# NguyenLi.net
KiCad netlist of a schematic drawn in Altium Designer
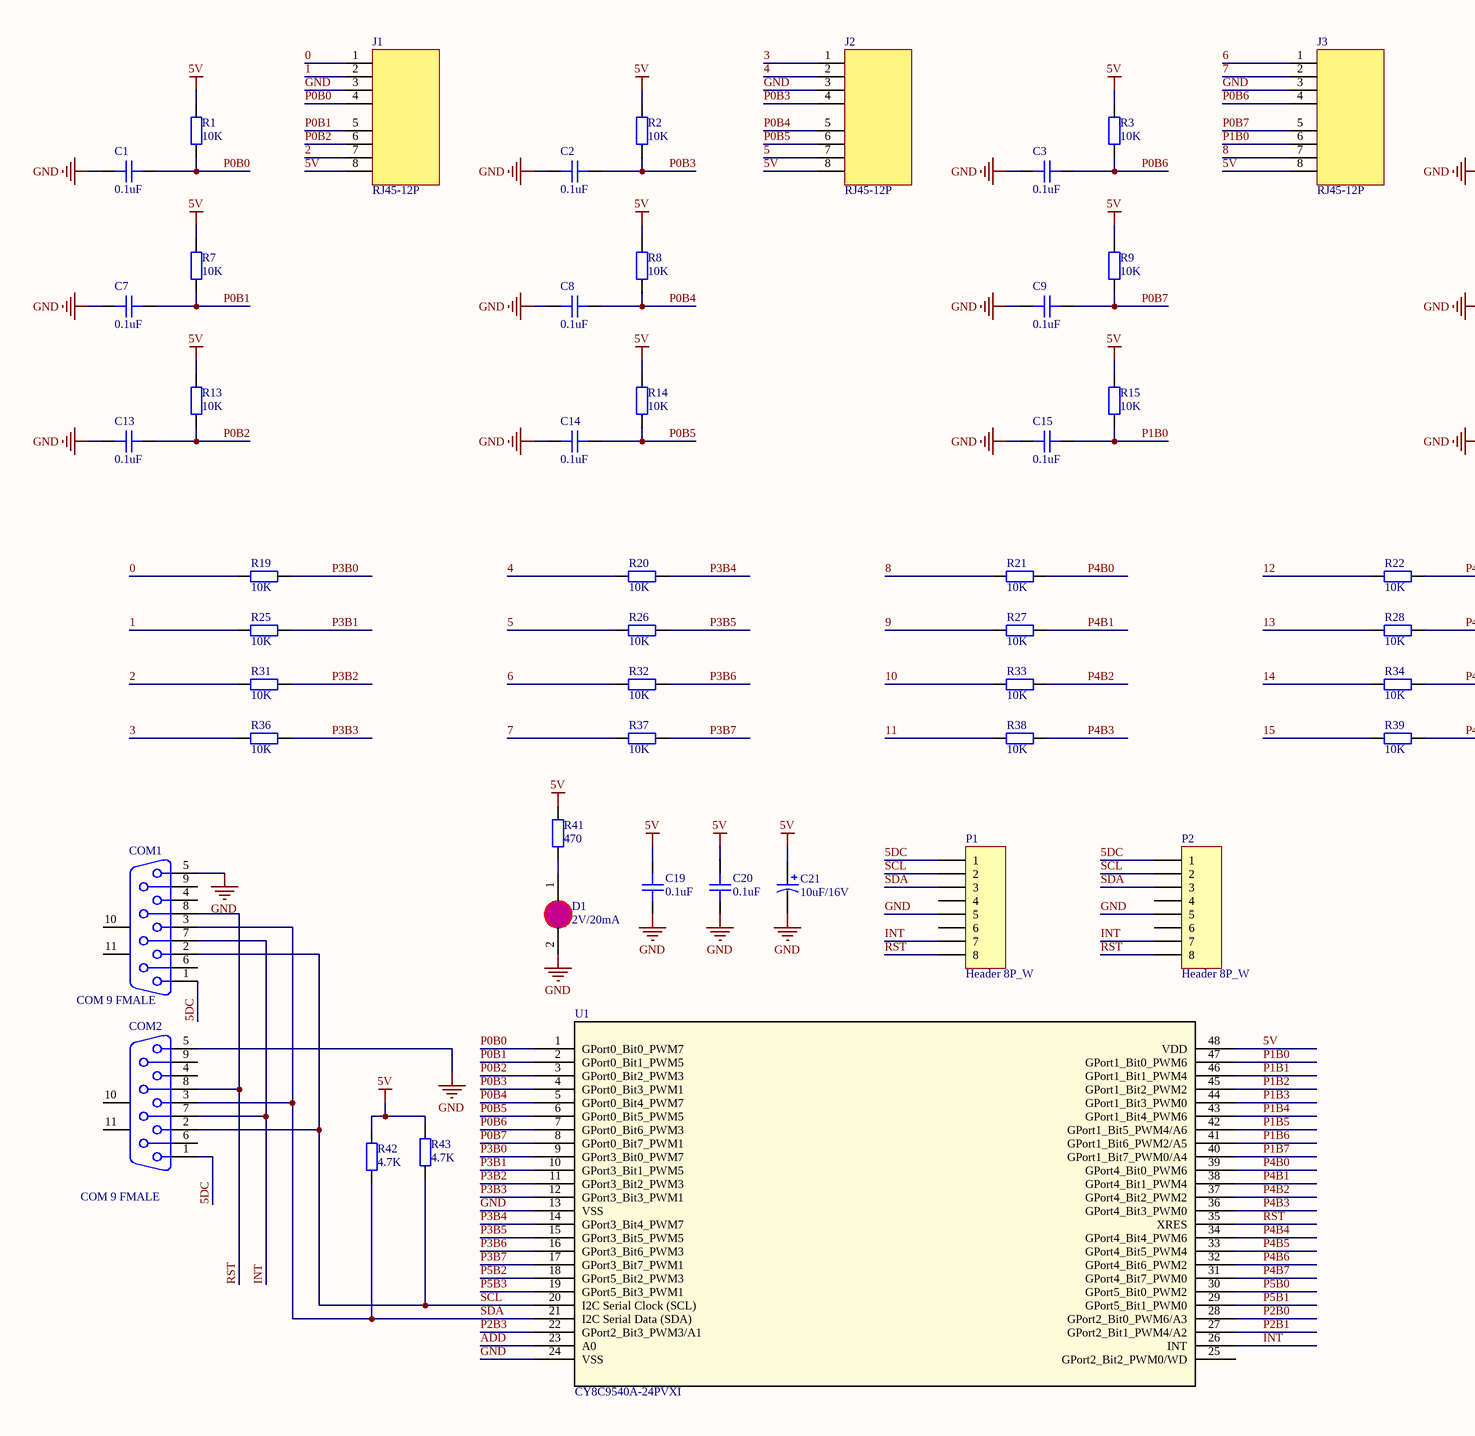
[diagram p0: NguyenLi.SchDoc, left]
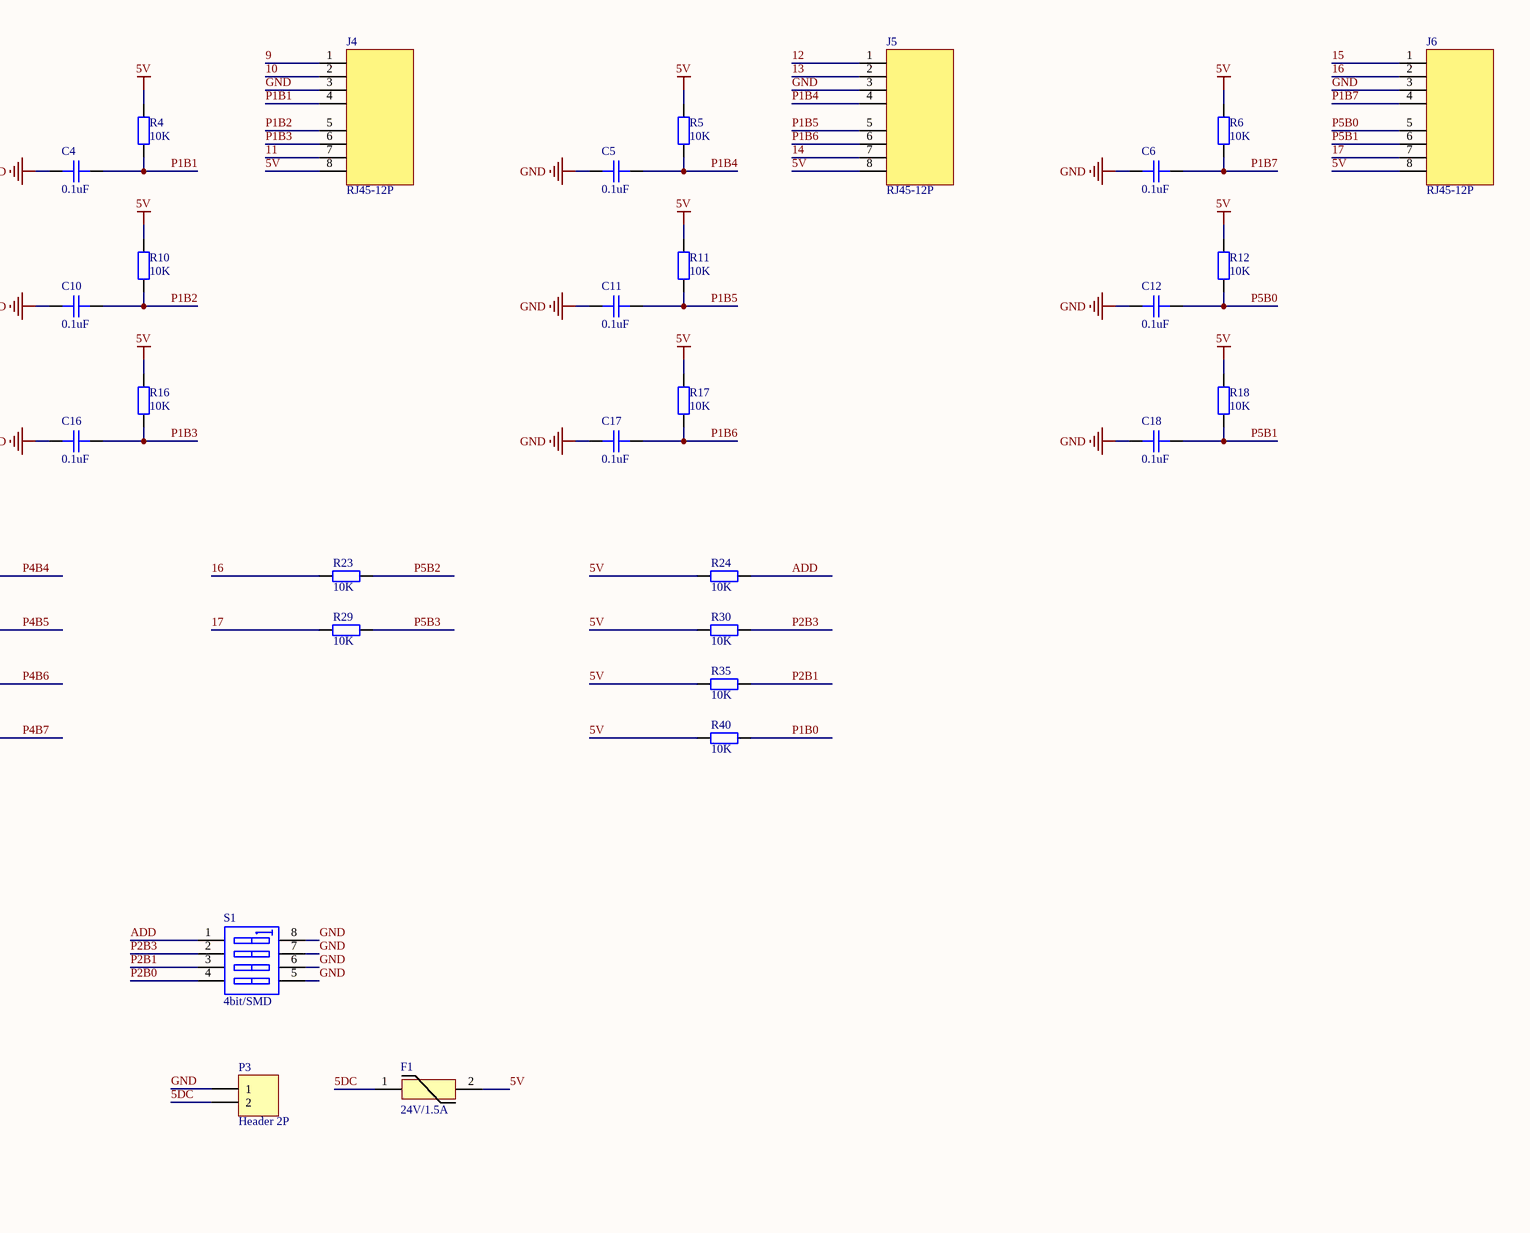
[diagram p1: NguyenLi.SchDoc, right]

(export (version "E")
  (design (tool "Eeschema 10.0.6"))
  (components
    (comp (ref "C1")
      (value "0.1uF")
      (footprint "CAPC-0603 (1608)")
      (description "CAP CER 0.1uF 50V 10% X7R 0603")
      (fields (field (name "MPN") "C0603C104K5RACTU"))
      (libsource (lib "BYTECH_HW_LIB_2019 (1) (1)") (part "C0603C104K5RACTU"))
    )
    (comp (ref "C2")
      (value "0.1uF")
      (footprint "CAPC-0603 (1608)")
      (description "CAP CER 0.1uF 50V 10% X7R 0603")
      (fields (field (name "MPN") "C0603C104K5RACTU"))
      (libsource (lib "BYTECH_HW_LIB_2019 (1) (1)") (part "C0603C104K5RACTU"))
    )
    (comp (ref "C3")
      (value "0.1uF")
      (footprint "CAPC-0603 (1608)")
      (description "CAP CER 0.1uF 50V 10% X7R 0603")
      (fields (field (name "MPN") "C0603C104K5RACTU"))
      (libsource (lib "BYTECH_HW_LIB_2019 (1) (1)") (part "C0603C104K5RACTU"))
    )
    (comp (ref "C4")
      (value "0.1uF")
      (footprint "CAPC-0603 (1608)")
      (description "CAP CER 0.1uF 50V 10% X7R 0603")
      (fields (field (name "MPN") "C0603C104K5RACTU"))
      (libsource (lib "BYTECH_HW_LIB_2019 (1) (1)") (part "C0603C104K5RACTU"))
    )
    (comp (ref "C5")
      (value "0.1uF")
      (footprint "CAPC-0603 (1608)")
      (description "CAP CER 0.1uF 50V 10% X7R 0603")
      (fields (field (name "MPN") "C0603C104K5RACTU"))
      (libsource (lib "BYTECH_HW_LIB_2019 (1) (1)") (part "C0603C104K5RACTU"))
    )
    (comp (ref "C6")
      (value "0.1uF")
      (footprint "CAPC-0603 (1608)")
      (description "CAP CER 0.1uF 50V 10% X7R 0603")
      (fields (field (name "MPN") "C0603C104K5RACTU"))
      (libsource (lib "BYTECH_HW_LIB_2019 (1) (1)") (part "C0603C104K5RACTU"))
    )
    (comp (ref "C7")
      (value "0.1uF")
      (footprint "CAPC-0603 (1608)")
      (description "CAP CER 0.1uF 50V 10% X7R 0603")
      (fields (field (name "MPN") "C0603C104K5RACTU"))
      (libsource (lib "BYTECH_HW_LIB_2019 (1) (1)") (part "C0603C104K5RACTU"))
    )
    (comp (ref "C8")
      (value "0.1uF")
      (footprint "CAPC-0603 (1608)")
      (description "CAP CER 0.1uF 50V 10% X7R 0603")
      (fields (field (name "MPN") "C0603C104K5RACTU"))
      (libsource (lib "BYTECH_HW_LIB_2019 (1) (1)") (part "C0603C104K5RACTU"))
    )
    (comp (ref "C9")
      (value "0.1uF")
      (footprint "CAPC-0603 (1608)")
      (description "CAP CER 0.1uF 50V 10% X7R 0603")
      (fields (field (name "MPN") "C0603C104K5RACTU"))
      (libsource (lib "BYTECH_HW_LIB_2019 (1) (1)") (part "C0603C104K5RACTU"))
    )
    (comp (ref "C10")
      (value "0.1uF")
      (footprint "CAPC-0603 (1608)")
      (description "CAP CER 0.1uF 50V 10% X7R 0603")
      (fields (field (name "MPN") "C0603C104K5RACTU"))
      (libsource (lib "BYTECH_HW_LIB_2019 (1) (1)") (part "C0603C104K5RACTU"))
    )
    (comp (ref "C11")
      (value "0.1uF")
      (footprint "CAPC-0603 (1608)")
      (description "CAP CER 0.1uF 50V 10% X7R 0603")
      (fields (field (name "MPN") "C0603C104K5RACTU"))
      (libsource (lib "BYTECH_HW_LIB_2019 (1) (1)") (part "C0603C104K5RACTU"))
    )
    (comp (ref "C12")
      (value "0.1uF")
      (footprint "CAPC-0603 (1608)")
      (description "CAP CER 0.1uF 50V 10% X7R 0603")
      (fields (field (name "MPN") "C0603C104K5RACTU"))
      (libsource (lib "BYTECH_HW_LIB_2019 (1) (1)") (part "C0603C104K5RACTU"))
    )
    (comp (ref "C13")
      (value "0.1uF")
      (footprint "CAPC-0603 (1608)")
      (description "CAP CER 0.1uF 50V 10% X7R 0603")
      (fields (field (name "MPN") "C0603C104K5RACTU"))
      (libsource (lib "BYTECH_HW_LIB_2019 (1) (1)") (part "C0603C104K5RACTU"))
    )
    (comp (ref "C14")
      (value "0.1uF")
      (footprint "CAPC-0603 (1608)")
      (description "CAP CER 0.1uF 50V 10% X7R 0603")
      (fields (field (name "MPN") "C0603C104K5RACTU"))
      (libsource (lib "BYTECH_HW_LIB_2019 (1) (1)") (part "C0603C104K5RACTU"))
    )
    (comp (ref "C15")
      (value "0.1uF")
      (footprint "CAPC-0603 (1608)")
      (description "CAP CER 0.1uF 50V 10% X7R 0603")
      (fields (field (name "MPN") "C0603C104K5RACTU"))
      (libsource (lib "BYTECH_HW_LIB_2019 (1) (1)") (part "C0603C104K5RACTU"))
    )
    (comp (ref "C16")
      (value "0.1uF")
      (footprint "CAPC-0603 (1608)")
      (description "CAP CER 0.1uF 50V 10% X7R 0603")
      (fields (field (name "MPN") "C0603C104K5RACTU"))
      (libsource (lib "BYTECH_HW_LIB_2019 (1) (1)") (part "C0603C104K5RACTU"))
    )
    (comp (ref "C17")
      (value "0.1uF")
      (footprint "CAPC-0603 (1608)")
      (description "CAP CER 0.1uF 50V 10% X7R 0603")
      (fields (field (name "MPN") "C0603C104K5RACTU"))
      (libsource (lib "BYTECH_HW_LIB_2019 (1) (1)") (part "C0603C104K5RACTU"))
    )
    (comp (ref "C18")
      (value "0.1uF")
      (footprint "CAPC-0603 (1608)")
      (description "CAP CER 0.1uF 50V 10% X7R 0603")
      (fields (field (name "MPN") "C0603C104K5RACTU"))
      (libsource (lib "BYTECH_HW_LIB_2019 (1) (1)") (part "C0603C104K5RACTU"))
    )
    (comp (ref "C19")
      (value "0.1uF")
      (footprint "CAPC-0603 (1608)")
      (description "CAP CER 0.1uF 50V 10% X7R 0603")
      (fields (field (name "MPN") "C0603C104K5RACTU"))
      (libsource (lib "BYTECH_HW_LIB_2019 (1) (1)") (part "C0603C104K5RACTU"))
    )
    (comp (ref "C20")
      (value "0.1uF")
      (footprint "CAPC-0603 (1608)")
      (description "CAP CER 0.1uF 50V 10% X7R 0603")
      (fields (field (name "MPN") "C0603C104K5RACTU"))
      (libsource (lib "BYTECH_HW_LIB_2019 (1) (1)") (part "C0603C104K5RACTU"))
    )
    (comp (ref "C21")
      (value "10uF/16V")
      (footprint "CAP_ALUM_D050_S20_H110")
      (description "CAP ALUM 10uF 50V 20% RADIAL")
      (fields (field (name "MPN") "106CKR050M"))
      (libsource (lib "BYTECH_HW_LIB_2019 (1) (1)") (part "106CKR050M"))
    )
    (comp (ref "COM1")
      (value "COM 9 FMALE")
      (footprint "DSB 9-F")
      (description "COM 9")
      (fields (field (name "PUBLISHER") "Altium Limited"))
      (libsource (lib "My Library") (part "DSB9F"))
    )
    (comp (ref "COM2")
      (value "COM 9 FMALE")
      (footprint "DSB 9-F")
      (description "COM 9")
      (fields (field (name "PUBLISHER") "Altium Limited"))
      (libsource (lib "My Library") (part "DSB9F"))
    )
    (comp (ref "D1")
      (value "2V/20mA")
      (footprint "LED_0805_RED")
      (description "LED RED CLEAR 0805 SMD")
      (fields (field (name "MPN") "17-215SURC/S530-A3/TR8"))
      (libsource (lib "BYTECH_HW_LIB_2019 (1) (1)") (part "17-215SURC/S530-A3/TR8"))
    )
    (comp (ref "F1")
      (value "24V/1.5A")
      (footprint "FUSE_1812(4532)")
      (description "FUSE PTC RESETTABLE 24V 1.50A 1812L")
      (fields (field (name "MPN") "1812L150/24MR"))
      (libsource (lib "BYTECH_HW_LIB_2019 (1) (1)") (part "1812L150/24MR"))
    )
    (comp (ref "J1")
      (value "RJ45-12P")
      (footprint "RJ45-8PIN_18MM_NO_TRANSFORMER")
      (libsource (lib "BYTECH_HW_LIB_2019 (1) (1)") (part "RJ45-12PIN_NO_TRANSFORMER"))
    )
    (comp (ref "J2")
      (value "RJ45-12P")
      (footprint "RJ45-8PIN_18MM_NO_TRANSFORMER")
      (libsource (lib "BYTECH_HW_LIB_2019 (1) (1)") (part "RJ45-12PIN_NO_TRANSFORMER"))
    )
    (comp (ref "J3")
      (value "RJ45-12P")
      (footprint "RJ45-8PIN_18MM_NO_TRANSFORMER")
      (libsource (lib "BYTECH_HW_LIB_2019 (1) (1)") (part "RJ45-12PIN_NO_TRANSFORMER"))
    )
    (comp (ref "J4")
      (value "RJ45-12P")
      (footprint "RJ45-8PIN_18MM_NO_TRANSFORMER")
      (libsource (lib "BYTECH_HW_LIB_2019 (1) (1)") (part "RJ45-12PIN_NO_TRANSFORMER"))
    )
    (comp (ref "J5")
      (value "RJ45-12P")
      (footprint "RJ45-8PIN_18MM_NO_TRANSFORMER")
      (libsource (lib "BYTECH_HW_LIB_2019 (1) (1)") (part "RJ45-12PIN_NO_TRANSFORMER"))
    )
    (comp (ref "J6")
      (value "RJ45-12P")
      (footprint "RJ45-8PIN_18MM_NO_TRANSFORMER")
      (libsource (lib "BYTECH_HW_LIB_2019 (1) (1)") (part "RJ45-12PIN_NO_TRANSFORMER"))
    )
    (comp (ref "P1")
      (value "Header 8P_W")
      (footprint "HDR1X8 - W")
      (description "Header, 8 Pin Pitch 2.54mm")
      (libsource (lib "Header-Connecter") (part "Header 8x1"))
    )
    (comp (ref "P2")
      (value "Header 8P_W")
      (footprint "HDR1X8 - W")
      (description "Header, 8 Pin Pitch 2.54mm")
      (libsource (lib "Header-Connecter") (part "Header 8x1"))
    )
    (comp (ref "P3")
      (value "Header 2P")
      (footprint "VH3.96-2P")
      (description "Header, 2 Pin Pitch 3.96mm")
      (fields (field (name "MPN") "VH3.96-2P"))
      (libsource (lib "BYTECH_HW_LIB_2019 (1) (1)") (part "VH3.96-2P"))
    )
    (comp (ref "R1")
      (value "10K")
      (footprint "RESC-0603 (1608)")
      (description "RES SMD 10K OHM 1% 1/10W 0603")
      (fields (field (name "MPN") "RC0603FR-0710KL"))
      (libsource (lib "") (part "RC0603FR-0710KL_1"))
    )
    (comp (ref "R2")
      (value "10K")
      (footprint "RESC-0603 (1608)")
      (description "RES SMD 10K OHM 1% 1/10W 0603")
      (fields (field (name "MPN") "RC0603FR-0710KL"))
      (libsource (lib "") (part "RC0603FR-0710KL_1"))
    )
    (comp (ref "R3")
      (value "10K")
      (footprint "RESC-0603 (1608)")
      (description "RES SMD 10K OHM 1% 1/10W 0603")
      (fields (field (name "MPN") "RC0603FR-0710KL"))
      (libsource (lib "") (part "RC0603FR-0710KL_1"))
    )
    (comp (ref "R4")
      (value "10K")
      (footprint "RESC-0603 (1608)")
      (description "RES SMD 10K OHM 1% 1/10W 0603")
      (fields (field (name "MPN") "RC0603FR-0710KL"))
      (libsource (lib "") (part "RC0603FR-0710KL_1"))
    )
    (comp (ref "R5")
      (value "10K")
      (footprint "RESC-0603 (1608)")
      (description "RES SMD 10K OHM 1% 1/10W 0603")
      (fields (field (name "MPN") "RC0603FR-0710KL"))
      (libsource (lib "") (part "RC0603FR-0710KL_1"))
    )
    (comp (ref "R6")
      (value "10K")
      (footprint "RESC-0603 (1608)")
      (description "RES SMD 10K OHM 1% 1/10W 0603")
      (fields (field (name "MPN") "RC0603FR-0710KL"))
      (libsource (lib "") (part "RC0603FR-0710KL_1"))
    )
    (comp (ref "R7")
      (value "10K")
      (footprint "RESC-0603 (1608)")
      (description "RES SMD 10K OHM 1% 1/10W 0603")
      (fields (field (name "MPN") "RC0603FR-0710KL"))
      (libsource (lib "") (part "RC0603FR-0710KL_1"))
    )
    (comp (ref "R8")
      (value "10K")
      (footprint "RESC-0603 (1608)")
      (description "RES SMD 10K OHM 1% 1/10W 0603")
      (fields (field (name "MPN") "RC0603FR-0710KL"))
      (libsource (lib "") (part "RC0603FR-0710KL_1"))
    )
    (comp (ref "R9")
      (value "10K")
      (footprint "RESC-0603 (1608)")
      (description "RES SMD 10K OHM 1% 1/10W 0603")
      (fields (field (name "MPN") "RC0603FR-0710KL"))
      (libsource (lib "") (part "RC0603FR-0710KL_1"))
    )
    (comp (ref "R10")
      (value "10K")
      (footprint "RESC-0603 (1608)")
      (description "RES SMD 10K OHM 1% 1/10W 0603")
      (fields (field (name "MPN") "RC0603FR-0710KL"))
      (libsource (lib "") (part "RC0603FR-0710KL_1"))
    )
    (comp (ref "R11")
      (value "10K")
      (footprint "RESC-0603 (1608)")
      (description "RES SMD 10K OHM 1% 1/10W 0603")
      (fields (field (name "MPN") "RC0603FR-0710KL"))
      (libsource (lib "") (part "RC0603FR-0710KL_1"))
    )
    (comp (ref "R12")
      (value "10K")
      (footprint "RESC-0603 (1608)")
      (description "RES SMD 10K OHM 1% 1/10W 0603")
      (fields (field (name "MPN") "RC0603FR-0710KL"))
      (libsource (lib "") (part "RC0603FR-0710KL_1"))
    )
    (comp (ref "R13")
      (value "10K")
      (footprint "RESC-0603 (1608)")
      (description "RES SMD 10K OHM 1% 1/10W 0603")
      (fields (field (name "MPN") "RC0603FR-0710KL"))
      (libsource (lib "") (part "RC0603FR-0710KL_1"))
    )
    (comp (ref "R14")
      (value "10K")
      (footprint "RESC-0603 (1608)")
      (description "RES SMD 10K OHM 1% 1/10W 0603")
      (fields (field (name "MPN") "RC0603FR-0710KL"))
      (libsource (lib "") (part "RC0603FR-0710KL_1"))
    )
    (comp (ref "R15")
      (value "10K")
      (footprint "RESC-0603 (1608)")
      (description "RES SMD 10K OHM 1% 1/10W 0603")
      (fields (field (name "MPN") "RC0603FR-0710KL"))
      (libsource (lib "") (part "RC0603FR-0710KL_1"))
    )
    (comp (ref "R16")
      (value "10K")
      (footprint "RESC-0603 (1608)")
      (description "RES SMD 10K OHM 1% 1/10W 0603")
      (fields (field (name "MPN") "RC0603FR-0710KL"))
      (libsource (lib "") (part "RC0603FR-0710KL_1"))
    )
    (comp (ref "R17")
      (value "10K")
      (footprint "RESC-0603 (1608)")
      (description "RES SMD 10K OHM 1% 1/10W 0603")
      (fields (field (name "MPN") "RC0603FR-0710KL"))
      (libsource (lib "") (part "RC0603FR-0710KL_1"))
    )
    (comp (ref "R18")
      (value "10K")
      (footprint "RESC-0603 (1608)")
      (description "RES SMD 10K OHM 1% 1/10W 0603")
      (fields (field (name "MPN") "RC0603FR-0710KL"))
      (libsource (lib "") (part "RC0603FR-0710KL_1"))
    )
    (comp (ref "R19")
      (value "10K")
      (footprint "RESC-0603 (1608)")
      (description "RES SMD 10K OHM 1% 1/10W 0603")
      (fields (field (name "MPN") "RC0603FR-0710KL"))
      (libsource (lib "BYTECH_HW_LIB_2019 (1) (1)") (part "RC0603FR-0710KL"))
    )
    (comp (ref "R20")
      (value "10K")
      (footprint "RESC-0603 (1608)")
      (description "RES SMD 10K OHM 1% 1/10W 0603")
      (fields (field (name "MPN") "RC0603FR-0710KL"))
      (libsource (lib "BYTECH_HW_LIB_2019 (1) (1)") (part "RC0603FR-0710KL"))
    )
    (comp (ref "R21")
      (value "10K")
      (footprint "RESC-0603 (1608)")
      (description "RES SMD 10K OHM 1% 1/10W 0603")
      (fields (field (name "MPN") "RC0603FR-0710KL"))
      (libsource (lib "BYTECH_HW_LIB_2019 (1) (1)") (part "RC0603FR-0710KL"))
    )
    (comp (ref "R22")
      (value "10K")
      (footprint "RESC-0603 (1608)")
      (description "RES SMD 10K OHM 1% 1/10W 0603")
      (fields (field (name "MPN") "RC0603FR-0710KL"))
      (libsource (lib "BYTECH_HW_LIB_2019 (1) (1)") (part "RC0603FR-0710KL"))
    )
    (comp (ref "R23")
      (value "10K")
      (footprint "RESC-0603 (1608)")
      (description "RES SMD 10K OHM 1% 1/10W 0603")
      (fields (field (name "MPN") "RC0603FR-0710KL"))
      (libsource (lib "BYTECH_HW_LIB_2019 (1) (1)") (part "RC0603FR-0710KL"))
    )
    (comp (ref "R24")
      (value "10K")
      (footprint "RESC-0603 (1608)")
      (description "RES SMD 10K OHM 1% 1/10W 0603")
      (fields (field (name "MPN") "RC0603FR-0710KL"))
      (libsource (lib "BYTECH_HW_LIB_2019 (1) (1)") (part "RC0603FR-0710KL"))
    )
    (comp (ref "R25")
      (value "10K")
      (footprint "RESC-0603 (1608)")
      (description "RES SMD 10K OHM 1% 1/10W 0603")
      (fields (field (name "MPN") "RC0603FR-0710KL"))
      (libsource (lib "BYTECH_HW_LIB_2019 (1) (1)") (part "RC0603FR-0710KL"))
    )
    (comp (ref "R26")
      (value "10K")
      (footprint "RESC-0603 (1608)")
      (description "RES SMD 10K OHM 1% 1/10W 0603")
      (fields (field (name "MPN") "RC0603FR-0710KL"))
      (libsource (lib "BYTECH_HW_LIB_2019 (1) (1)") (part "RC0603FR-0710KL"))
    )
    (comp (ref "R27")
      (value "10K")
      (footprint "RESC-0603 (1608)")
      (description "RES SMD 10K OHM 1% 1/10W 0603")
      (fields (field (name "MPN") "RC0603FR-0710KL"))
      (libsource (lib "BYTECH_HW_LIB_2019 (1) (1)") (part "RC0603FR-0710KL"))
    )
    (comp (ref "R28")
      (value "10K")
      (footprint "RESC-0603 (1608)")
      (description "RES SMD 10K OHM 1% 1/10W 0603")
      (fields (field (name "MPN") "RC0603FR-0710KL"))
      (libsource (lib "BYTECH_HW_LIB_2019 (1) (1)") (part "RC0603FR-0710KL"))
    )
    (comp (ref "R29")
      (value "10K")
      (footprint "RESC-0603 (1608)")
      (description "RES SMD 10K OHM 1% 1/10W 0603")
      (fields (field (name "MPN") "RC0603FR-0710KL"))
      (libsource (lib "BYTECH_HW_LIB_2019 (1) (1)") (part "RC0603FR-0710KL"))
    )
    (comp (ref "R30")
      (value "10K")
      (footprint "RESC-0603 (1608)")
      (description "RES SMD 10K OHM 1% 1/10W 0603")
      (fields (field (name "MPN") "RC0603FR-0710KL"))
      (libsource (lib "BYTECH_HW_LIB_2019 (1) (1)") (part "RC0603FR-0710KL"))
    )
    (comp (ref "R31")
      (value "10K")
      (footprint "RESC-0603 (1608)")
      (description "RES SMD 10K OHM 1% 1/10W 0603")
      (fields (field (name "MPN") "RC0603FR-0710KL"))
      (libsource (lib "BYTECH_HW_LIB_2019 (1) (1)") (part "RC0603FR-0710KL"))
    )
    (comp (ref "R32")
      (value "10K")
      (footprint "RESC-0603 (1608)")
      (description "RES SMD 10K OHM 1% 1/10W 0603")
      (fields (field (name "MPN") "RC0603FR-0710KL"))
      (libsource (lib "BYTECH_HW_LIB_2019 (1) (1)") (part "RC0603FR-0710KL"))
    )
    (comp (ref "R33")
      (value "10K")
      (footprint "RESC-0603 (1608)")
      (description "RES SMD 10K OHM 1% 1/10W 0603")
      (fields (field (name "MPN") "RC0603FR-0710KL"))
      (libsource (lib "BYTECH_HW_LIB_2019 (1) (1)") (part "RC0603FR-0710KL"))
    )
    (comp (ref "R34")
      (value "10K")
      (footprint "RESC-0603 (1608)")
      (description "RES SMD 10K OHM 1% 1/10W 0603")
      (fields (field (name "MPN") "RC0603FR-0710KL"))
      (libsource (lib "BYTECH_HW_LIB_2019 (1) (1)") (part "RC0603FR-0710KL"))
    )
    (comp (ref "R35")
      (value "10K")
      (footprint "RESC-0603 (1608)")
      (description "RES SMD 10K OHM 1% 1/10W 0603")
      (fields (field (name "MPN") "RC0603FR-0710KL"))
      (libsource (lib "BYTECH_HW_LIB_2019 (1) (1)") (part "RC0603FR-0710KL"))
    )
    (comp (ref "R36")
      (value "10K")
      (footprint "RESC-0603 (1608)")
      (description "RES SMD 10K OHM 1% 1/10W 0603")
      (fields (field (name "MPN") "RC0603FR-0710KL"))
      (libsource (lib "BYTECH_HW_LIB_2019 (1) (1)") (part "RC0603FR-0710KL"))
    )
    (comp (ref "R37")
      (value "10K")
      (footprint "RESC-0603 (1608)")
      (description "RES SMD 10K OHM 1% 1/10W 0603")
      (fields (field (name "MPN") "RC0603FR-0710KL"))
      (libsource (lib "BYTECH_HW_LIB_2019 (1) (1)") (part "RC0603FR-0710KL"))
    )
    (comp (ref "R38")
      (value "10K")
      (footprint "RESC-0603 (1608)")
      (description "RES SMD 10K OHM 1% 1/10W 0603")
      (fields (field (name "MPN") "RC0603FR-0710KL"))
      (libsource (lib "BYTECH_HW_LIB_2019 (1) (1)") (part "RC0603FR-0710KL"))
    )
    (comp (ref "R39")
      (value "10K")
      (footprint "RESC-0603 (1608)")
      (description "RES SMD 10K OHM 1% 1/10W 0603")
      (fields (field (name "MPN") "RC0603FR-0710KL"))
      (libsource (lib "BYTECH_HW_LIB_2019 (1) (1)") (part "RC0603FR-0710KL"))
    )
    (comp (ref "R40")
      (value "10K")
      (footprint "RESC-0603 (1608)")
      (description "RES SMD 10K OHM 1% 1/10W 0603")
      (fields (field (name "MPN") "RC0603FR-0710KL"))
      (libsource (lib "BYTECH_HW_LIB_2019 (1) (1)") (part "RC0603FR-0710KL"))
    )
    (comp (ref "R41")
      (value "470")
      (footprint "RESC-0603 (1608)")
      (description "RES SMD 470 OHM 1% 1/10W 0603")
      (fields (field (name "MPN") "RC0603FR-07470RL"))
      (libsource (lib "BYTECH_HW_LIB_2019 (1) (1)") (part "RC0603FR-07470RL"))
    )
    (comp (ref "R42")
      (value "4.7K")
      (footprint "RESC-0603 (1608)")
      (description "RES SMD 470 OHM 1% 1/10W 0603")
      (fields (field (name "MPN") "RC0603FR-07470RL"))
      (libsource (lib "BYTECH_HW_LIB_2019 (1) (1)") (part "RC0603FR-07470RL"))
    )
    (comp (ref "R43")
      (value "4.7K")
      (footprint "RESC-0603 (1608)")
      (description "RES SMD 470 OHM 1% 1/10W 0603")
      (fields (field (name "MPN") "RC0603FR-07470RL"))
      (libsource (lib "BYTECH_HW_LIB_2019 (1) (1)") (part "RC0603FR-07470RL"))
    )
    (comp (ref "S1")
      (value "4bit/SMD")
      (footprint "219-4LPSTR")
      (description "SWITCH SLIDE DIP SPST 100MA 20V")
      (fields (field (name "MPN") "219-4LPSTR"))
      (libsource (lib "BYTECH_HW_LIB_2019 (1) (1)") (part "219-4LPSTR"))
    )
    (comp (ref "U1")
      (value "CY8C9540A-24PVXI")
      (footprint "SSOP-48")
      (description "No Description Available")
      (libsource (lib "CY8C9540A-24PVXI") (part "CY8C9540A-24PVXI"))
    )
  )
  (nets
    (net (code "1") (name "/0") (class "Default")
      (node (ref "J1") (pin "1") (pintype "passive"))
      (node (ref "R19") (pin "1") (pinfunction "1_1") (pintype "passive"))
    )
    (net (code "2") (name "/1") (class "Default")
      (node (ref "J1") (pin "2") (pintype "passive"))
      (node (ref "R25") (pin "1") (pinfunction "1_1") (pintype "passive"))
    )
    (net (code "3") (name "/2") (class "Default")
      (node (ref "J1") (pin "7") (pintype "passive"))
      (node (ref "R31") (pin "1") (pinfunction "1_1") (pintype "passive"))
    )
    (net (code "4") (name "/3") (class "Default")
      (node (ref "J2") (pin "1") (pintype "passive"))
      (node (ref "R36") (pin "1") (pinfunction "1_1") (pintype "passive"))
    )
    (net (code "5") (name "/4") (class "Default")
      (node (ref "J2") (pin "2") (pintype "passive"))
      (node (ref "R20") (pin "1") (pinfunction "1_1") (pintype "passive"))
    )
    (net (code "6") (name "/5") (class "Default")
      (node (ref "J2") (pin "7") (pintype "passive"))
      (node (ref "R26") (pin "1") (pinfunction "1_1") (pintype "passive"))
    )
    (net (code "7") (name "/5DC") (class "Default")
      (node (ref "COM1") (pin "1") (pinfunction "1_1") (pintype "passive"))
      (node (ref "COM2") (pin "1") (pinfunction "1_1") (pintype "passive"))
      (node (ref "F1") (pin "1") (pinfunction "1_1") (pintype "passive"))
      (node (ref "P1") (pin "1") (pinfunction "1_1") (pintype "passive"))
      (node (ref "P2") (pin "1") (pinfunction "1_1") (pintype "passive"))
      (node (ref "P3") (pin "2") (pinfunction "2_2") (pintype "passive"))
    )
    (net (code "8") (name "/6") (class "Default")
      (node (ref "J3") (pin "1") (pintype "passive"))
      (node (ref "R32") (pin "1") (pinfunction "1_1") (pintype "passive"))
    )
    (net (code "9") (name "/7") (class "Default")
      (node (ref "J3") (pin "2") (pintype "passive"))
      (node (ref "R37") (pin "1") (pinfunction "1_1") (pintype "passive"))
    )
    (net (code "10") (name "/8") (class "Default")
      (node (ref "J3") (pin "7") (pintype "passive"))
      (node (ref "R21") (pin "1") (pinfunction "1_1") (pintype "passive"))
    )
    (net (code "11") (name "/9") (class "Default")
      (node (ref "J4") (pin "1") (pintype "passive"))
      (node (ref "R27") (pin "1") (pinfunction "1_1") (pintype "passive"))
    )
    (net (code "12") (name "/10") (class "Default")
      (node (ref "J4") (pin "2") (pintype "passive"))
      (node (ref "R33") (pin "1") (pinfunction "1_1") (pintype "passive"))
    )
    (net (code "13") (name "/11") (class "Default")
      (node (ref "J4") (pin "7") (pintype "passive"))
      (node (ref "R38") (pin "1") (pinfunction "1_1") (pintype "passive"))
    )
    (net (code "14") (name "/12") (class "Default")
      (node (ref "J5") (pin "1") (pintype "passive"))
      (node (ref "R22") (pin "1") (pinfunction "1_1") (pintype "passive"))
    )
    (net (code "15") (name "/13") (class "Default")
      (node (ref "J5") (pin "2") (pintype "passive"))
      (node (ref "R28") (pin "1") (pinfunction "1_1") (pintype "passive"))
    )
    (net (code "16") (name "/14") (class "Default")
      (node (ref "J5") (pin "7") (pintype "passive"))
      (node (ref "R34") (pin "1") (pinfunction "1_1") (pintype "passive"))
    )
    (net (code "17") (name "/15") (class "Default")
      (node (ref "J6") (pin "1") (pintype "passive"))
      (node (ref "R39") (pin "1") (pinfunction "1_1") (pintype "passive"))
    )
    (net (code "18") (name "/16") (class "Default")
      (node (ref "J6") (pin "2") (pintype "passive"))
      (node (ref "R23") (pin "1") (pinfunction "1_1") (pintype "passive"))
    )
    (net (code "19") (name "/17") (class "Default")
      (node (ref "J6") (pin "7") (pintype "passive"))
      (node (ref "R29") (pin "1") (pinfunction "1_1") (pintype "passive"))
    )
    (net (code "21") (name "/ADD") (class "Default")
      (node (ref "R24") (pin "2") (pinfunction "2_2") (pintype "passive"))
      (node (ref "S1") (pin "1") (pinfunction "A1_1") (pintype "passive"))
      (node (ref "U1") (pin "23") (pinfunction "A0_23") (pintype "passive"))
    )
    (net (code "22") (name "/INT") (class "Default")
      (node (ref "COM1") (pin "7") (pinfunction "7_7") (pintype "passive"))
      (node (ref "COM2") (pin "7") (pinfunction "7_7") (pintype "passive"))
      (node (ref "P1") (pin "7") (pinfunction "7_7") (pintype "passive"))
      (node (ref "P2") (pin "7") (pinfunction "7_7") (pintype "passive"))
      (node (ref "U1") (pin "26") (pinfunction "INT_26") (pintype "passive"))
    )
    (net (code "23") (name "/P0B0") (class "Default")
      (node (ref "C1") (pin "2") (pinfunction "2_2") (pintype "passive"))
      (node (ref "J1") (pin "4") (pintype "passive"))
      (node (ref "R1") (pin "1") (pinfunction "1_1") (pintype "passive"))
      (node (ref "U1") (pin "1") (pinfunction "GPort0_Bit0_PWM7_1") (pintype "passive"))
    )
    (net (code "24") (name "/P0B1") (class "Default")
      (node (ref "C7") (pin "2") (pinfunction "2_2") (pintype "passive"))
      (node (ref "J1") (pin "5") (pintype "passive"))
      (node (ref "R7") (pin "1") (pinfunction "1_1") (pintype "passive"))
      (node (ref "U1") (pin "2") (pinfunction "GPort0_Bit1_PWM5_2") (pintype "passive"))
    )
    (net (code "25") (name "/P0B2") (class "Default")
      (node (ref "C13") (pin "2") (pinfunction "2_2") (pintype "passive"))
      (node (ref "J1") (pin "6") (pintype "passive"))
      (node (ref "R13") (pin "1") (pinfunction "1_1") (pintype "passive"))
      (node (ref "U1") (pin "3") (pinfunction "GPort0_Bit2_PWM3_3") (pintype "passive"))
    )
    (net (code "26") (name "/P0B3") (class "Default")
      (node (ref "C2") (pin "2") (pinfunction "2_2") (pintype "passive"))
      (node (ref "J2") (pin "4") (pintype "passive"))
      (node (ref "R2") (pin "1") (pinfunction "1_1") (pintype "passive"))
      (node (ref "U1") (pin "4") (pinfunction "GPort0_Bit3_PWM1_4") (pintype "passive"))
    )
    (net (code "27") (name "/P0B4") (class "Default")
      (node (ref "C8") (pin "2") (pinfunction "2_2") (pintype "passive"))
      (node (ref "J2") (pin "5") (pintype "passive"))
      (node (ref "R8") (pin "1") (pinfunction "1_1") (pintype "passive"))
      (node (ref "U1") (pin "5") (pinfunction "GPort0_Bit4_PWM7_5") (pintype "passive"))
    )
    (net (code "28") (name "/P0B5") (class "Default")
      (node (ref "C14") (pin "2") (pinfunction "2_2") (pintype "passive"))
      (node (ref "J2") (pin "6") (pintype "passive"))
      (node (ref "R14") (pin "1") (pinfunction "1_1") (pintype "passive"))
      (node (ref "U1") (pin "6") (pinfunction "GPort0_Bit5_PWM5_6") (pintype "passive"))
    )
    (net (code "29") (name "/P0B6") (class "Default")
      (node (ref "C3") (pin "2") (pinfunction "2_2") (pintype "passive"))
      (node (ref "J3") (pin "4") (pintype "passive"))
      (node (ref "R3") (pin "1") (pinfunction "1_1") (pintype "passive"))
      (node (ref "U1") (pin "7") (pinfunction "GPort0_Bit6_PWM3_7") (pintype "passive"))
    )
    (net (code "30") (name "/P0B7") (class "Default")
      (node (ref "C9") (pin "2") (pinfunction "2_2") (pintype "passive"))
      (node (ref "J3") (pin "5") (pintype "passive"))
      (node (ref "R9") (pin "1") (pinfunction "1_1") (pintype "passive"))
      (node (ref "U1") (pin "8") (pinfunction "GPort0_Bit7_PWM1_8") (pintype "passive"))
    )
    (net (code "31") (name "/P1B0") (class "Default")
      (node (ref "C15") (pin "2") (pinfunction "2_2") (pintype "passive"))
      (node (ref "J3") (pin "6") (pintype "passive"))
      (node (ref "R15") (pin "1") (pinfunction "1_1") (pintype "passive"))
      (node (ref "R40") (pin "2") (pinfunction "2_2") (pintype "passive"))
      (node (ref "U1") (pin "47") (pinfunction "GPort1_Bit0_PWM6_47") (pintype "passive"))
    )
    (net (code "32") (name "/P1B1") (class "Default")
      (node (ref "C4") (pin "2") (pinfunction "2_2") (pintype "passive"))
      (node (ref "J4") (pin "4") (pintype "passive"))
      (node (ref "R4") (pin "1") (pinfunction "1_1") (pintype "passive"))
      (node (ref "U1") (pin "46") (pinfunction "GPort1_Bit1_PWM4_46") (pintype "passive"))
    )
    (net (code "33") (name "/P1B2") (class "Default")
      (node (ref "C10") (pin "2") (pinfunction "2_2") (pintype "passive"))
      (node (ref "J4") (pin "5") (pintype "passive"))
      (node (ref "R10") (pin "1") (pinfunction "1_1") (pintype "passive"))
      (node (ref "U1") (pin "45") (pinfunction "GPort1_Bit2_PWM2_45") (pintype "passive"))
    )
    (net (code "34") (name "/P1B3") (class "Default")
      (node (ref "C16") (pin "2") (pinfunction "2_2") (pintype "passive"))
      (node (ref "J4") (pin "6") (pintype "passive"))
      (node (ref "R16") (pin "1") (pinfunction "1_1") (pintype "passive"))
      (node (ref "U1") (pin "44") (pinfunction "GPort1_Bit3_PWM0_44") (pintype "passive"))
    )
    (net (code "35") (name "/P1B4") (class "Default")
      (node (ref "C5") (pin "2") (pinfunction "2_2") (pintype "passive"))
      (node (ref "J5") (pin "4") (pintype "passive"))
      (node (ref "R5") (pin "1") (pinfunction "1_1") (pintype "passive"))
      (node (ref "U1") (pin "43") (pinfunction "GPort1_Bit4_PWM6_43") (pintype "passive"))
    )
    (net (code "36") (name "/P1B5") (class "Default")
      (node (ref "C11") (pin "2") (pinfunction "2_2") (pintype "passive"))
      (node (ref "J5") (pin "5") (pintype "passive"))
      (node (ref "R11") (pin "1") (pinfunction "1_1") (pintype "passive"))
      (node (ref "U1") (pin "42") (pinfunction "GPort1_Bit5_PWM4/A6_42") (pintype "passive"))
    )
    (net (code "37") (name "/P1B6") (class "Default")
      (node (ref "C17") (pin "2") (pinfunction "2_2") (pintype "passive"))
      (node (ref "J5") (pin "6") (pintype "passive"))
      (node (ref "R17") (pin "1") (pinfunction "1_1") (pintype "passive"))
      (node (ref "U1") (pin "41") (pinfunction "GPort1_Bit6_PWM2/A5_41") (pintype "passive"))
    )
    (net (code "38") (name "/P1B7") (class "Default")
      (node (ref "C6") (pin "2") (pinfunction "2_2") (pintype "passive"))
      (node (ref "J6") (pin "4") (pintype "passive"))
      (node (ref "R6") (pin "1") (pinfunction "1_1") (pintype "passive"))
      (node (ref "U1") (pin "40") (pinfunction "GPort1_Bit7_PWM0/A4_40") (pintype "passive"))
    )
    (net (code "39") (name "/P2B0") (class "Default")
      (node (ref "S1") (pin "4") (pinfunction "A4_4") (pintype "passive"))
      (node (ref "U1") (pin "28") (pinfunction "GPort2_Bit0_PWM6/A3_28") (pintype "passive"))
    )
    (net (code "40") (name "/P2B1") (class "Default")
      (node (ref "R35") (pin "2") (pinfunction "2_2") (pintype "passive"))
      (node (ref "S1") (pin "3") (pinfunction "A3_3") (pintype "passive"))
      (node (ref "U1") (pin "27") (pinfunction "GPort2_Bit1_PWM4/A2_27") (pintype "passive"))
    )
    (net (code "41") (name "/P2B3") (class "Default")
      (node (ref "R30") (pin "2") (pinfunction "2_2") (pintype "passive"))
      (node (ref "S1") (pin "2") (pinfunction "A2_2") (pintype "passive"))
      (node (ref "U1") (pin "22") (pinfunction "GPort2_Bit3_PWM3/A1_22") (pintype "passive"))
    )
    (net (code "42") (name "/P3B0") (class "Default")
      (node (ref "R19") (pin "2") (pinfunction "2_2") (pintype "passive"))
      (node (ref "U1") (pin "9") (pinfunction "GPort3_Bit0_PWM7_9") (pintype "passive"))
    )
    (net (code "43") (name "/P3B1") (class "Default")
      (node (ref "R25") (pin "2") (pinfunction "2_2") (pintype "passive"))
      (node (ref "U1") (pin "10") (pinfunction "GPort3_Bit1_PWM5_10") (pintype "passive"))
    )
    (net (code "44") (name "/P3B2") (class "Default")
      (node (ref "R31") (pin "2") (pinfunction "2_2") (pintype "passive"))
      (node (ref "U1") (pin "11") (pinfunction "GPort3_Bit2_PWM3_11") (pintype "passive"))
    )
    (net (code "45") (name "/P3B3") (class "Default")
      (node (ref "R36") (pin "2") (pinfunction "2_2") (pintype "passive"))
      (node (ref "U1") (pin "12") (pinfunction "GPort3_Bit3_PWM1_12") (pintype "passive"))
    )
    (net (code "46") (name "/P3B4") (class "Default")
      (node (ref "R20") (pin "2") (pinfunction "2_2") (pintype "passive"))
      (node (ref "U1") (pin "14") (pinfunction "GPort3_Bit4_PWM7_14") (pintype "passive"))
    )
    (net (code "47") (name "/P3B5") (class "Default")
      (node (ref "R26") (pin "2") (pinfunction "2_2") (pintype "passive"))
      (node (ref "U1") (pin "15") (pinfunction "GPort3_Bit5_PWM5_15") (pintype "passive"))
    )
    (net (code "48") (name "/P3B6") (class "Default")
      (node (ref "R32") (pin "2") (pinfunction "2_2") (pintype "passive"))
      (node (ref "U1") (pin "16") (pinfunction "GPort3_Bit6_PWM3_16") (pintype "passive"))
    )
    (net (code "49") (name "/P3B7") (class "Default")
      (node (ref "R37") (pin "2") (pinfunction "2_2") (pintype "passive"))
      (node (ref "U1") (pin "17") (pinfunction "GPort3_Bit7_PWM1_17") (pintype "passive"))
    )
    (net (code "50") (name "/P4B0") (class "Default")
      (node (ref "R21") (pin "2") (pinfunction "2_2") (pintype "passive"))
      (node (ref "U1") (pin "39") (pinfunction "GPort4_Bit0_PWM6_39") (pintype "passive"))
    )
    (net (code "51") (name "/P4B1") (class "Default")
      (node (ref "R27") (pin "2") (pinfunction "2_2") (pintype "passive"))
      (node (ref "U1") (pin "38") (pinfunction "GPort4_Bit1_PWM4_38") (pintype "passive"))
    )
    (net (code "52") (name "/P4B2") (class "Default")
      (node (ref "R33") (pin "2") (pinfunction "2_2") (pintype "passive"))
      (node (ref "U1") (pin "37") (pinfunction "GPort4_Bit2_PWM2_37") (pintype "passive"))
    )
    (net (code "53") (name "/P4B3") (class "Default")
      (node (ref "R38") (pin "2") (pinfunction "2_2") (pintype "passive"))
      (node (ref "U1") (pin "36") (pinfunction "GPort4_Bit3_PWM0_36") (pintype "passive"))
    )
    (net (code "54") (name "/P4B4") (class "Default")
      (node (ref "R22") (pin "2") (pinfunction "2_2") (pintype "passive"))
      (node (ref "U1") (pin "34") (pinfunction "GPort4_Bit4_PWM6_34") (pintype "passive"))
    )
    (net (code "55") (name "/P4B5") (class "Default")
      (node (ref "R28") (pin "2") (pinfunction "2_2") (pintype "passive"))
      (node (ref "U1") (pin "33") (pinfunction "GPort4_Bit5_PWM4_33") (pintype "passive"))
    )
    (net (code "56") (name "/P4B6") (class "Default")
      (node (ref "R34") (pin "2") (pinfunction "2_2") (pintype "passive"))
      (node (ref "U1") (pin "32") (pinfunction "GPort4_Bit6_PWM2_32") (pintype "passive"))
    )
    (net (code "57") (name "/P4B7") (class "Default")
      (node (ref "R39") (pin "2") (pinfunction "2_2") (pintype "passive"))
      (node (ref "U1") (pin "31") (pinfunction "GPort4_Bit7_PWM0_31") (pintype "passive"))
    )
    (net (code "58") (name "/P5B0") (class "Default")
      (node (ref "C12") (pin "2") (pinfunction "2_2") (pintype "passive"))
      (node (ref "J6") (pin "5") (pintype "passive"))
      (node (ref "R12") (pin "1") (pinfunction "1_1") (pintype "passive"))
      (node (ref "U1") (pin "30") (pinfunction "GPort5_Bit0_PWM2_30") (pintype "passive"))
    )
    (net (code "59") (name "/P5B1") (class "Default")
      (node (ref "C18") (pin "2") (pinfunction "2_2") (pintype "passive"))
      (node (ref "J6") (pin "6") (pintype "passive"))
      (node (ref "R18") (pin "1") (pinfunction "1_1") (pintype "passive"))
      (node (ref "U1") (pin "29") (pinfunction "GPort5_Bit1_PWM0_29") (pintype "passive"))
    )
    (net (code "60") (name "/P5B2") (class "Default")
      (node (ref "R23") (pin "2") (pinfunction "2_2") (pintype "passive"))
      (node (ref "U1") (pin "18") (pinfunction "GPort5_Bit2_PWM3_18") (pintype "passive"))
    )
    (net (code "61") (name "/P5B3") (class "Default")
      (node (ref "R29") (pin "2") (pinfunction "2_2") (pintype "passive"))
      (node (ref "U1") (pin "19") (pinfunction "GPort5_Bit3_PWM1_19") (pintype "passive"))
    )
    (net (code "62") (name "/RST") (class "Default")
      (node (ref "COM1") (pin "8") (pinfunction "8_8") (pintype "passive"))
      (node (ref "COM2") (pin "8") (pinfunction "8_8") (pintype "passive"))
      (node (ref "P1") (pin "8") (pinfunction "8_8") (pintype "passive"))
      (node (ref "P2") (pin "8") (pinfunction "8_8") (pintype "passive"))
      (node (ref "U1") (pin "35") (pinfunction "XRES_35") (pintype "passive"))
    )
    (net (code "63") (name "/SCL") (class "Default")
      (node (ref "COM1") (pin "2") (pinfunction "2_2") (pintype "passive"))
      (node (ref "COM2") (pin "2") (pinfunction "2_2") (pintype "passive"))
      (node (ref "P1") (pin "2") (pinfunction "2_2") (pintype "passive"))
      (node (ref "P2") (pin "2") (pinfunction "2_2") (pintype "passive"))
      (node (ref "R43") (pin "1") (pinfunction "1_1") (pintype "passive"))
      (node (ref "U1") (pin "20") (pinfunction "I2C_Serial_Clock_(SCL)_20") (pintype "passive"))
    )
    (net (code "64") (name "/SDA") (class "Default")
      (node (ref "COM1") (pin "3") (pinfunction "3_3") (pintype "passive"))
      (node (ref "COM2") (pin "3") (pinfunction "3_3") (pintype "passive"))
      (node (ref "P1") (pin "3") (pinfunction "3_3") (pintype "passive"))
      (node (ref "P2") (pin "3") (pinfunction "3_3") (pintype "passive"))
      (node (ref "R42") (pin "1") (pinfunction "1_1") (pintype "passive"))
      (node (ref "U1") (pin "21") (pinfunction "I2C_Serial_Data_(SDA)_21") (pintype "passive"))
    )
    (net (code "65") (name "5V") (class "Default")
      (node (ref "C19") (pin "1") (pinfunction "1_1") (pintype "passive"))
      (node (ref "C20") (pin "2") (pinfunction "2_2") (pintype "passive"))
      (node (ref "C21") (pin "1") (pinfunction "1_1") (pintype "passive"))
      (node (ref "F1") (pin "2") (pinfunction "2_2") (pintype "passive"))
      (node (ref "J1") (pin "8") (pintype "passive"))
      (node (ref "J2") (pin "8") (pintype "passive"))
      (node (ref "J3") (pin "8") (pintype "passive"))
      (node (ref "J4") (pin "8") (pintype "passive"))
      (node (ref "J5") (pin "8") (pintype "passive"))
      (node (ref "J6") (pin "8") (pintype "passive"))
      (node (ref "R1") (pin "2") (pinfunction "2_2") (pintype "passive"))
      (node (ref "R10") (pin "2") (pinfunction "2_2") (pintype "passive"))
      (node (ref "R11") (pin "2") (pinfunction "2_2") (pintype "passive"))
      (node (ref "R12") (pin "2") (pinfunction "2_2") (pintype "passive"))
      (node (ref "R13") (pin "2") (pinfunction "2_2") (pintype "passive"))
      (node (ref "R14") (pin "2") (pinfunction "2_2") (pintype "passive"))
      (node (ref "R15") (pin "2") (pinfunction "2_2") (pintype "passive"))
      (node (ref "R16") (pin "2") (pinfunction "2_2") (pintype "passive"))
      (node (ref "R17") (pin "2") (pinfunction "2_2") (pintype "passive"))
      (node (ref "R18") (pin "2") (pinfunction "2_2") (pintype "passive"))
      (node (ref "R2") (pin "2") (pinfunction "2_2") (pintype "passive"))
      (node (ref "R24") (pin "1") (pinfunction "1_1") (pintype "passive"))
      (node (ref "R3") (pin "2") (pinfunction "2_2") (pintype "passive"))
      (node (ref "R30") (pin "1") (pinfunction "1_1") (pintype "passive"))
      (node (ref "R35") (pin "1") (pinfunction "1_1") (pintype "passive"))
      (node (ref "R4") (pin "2") (pinfunction "2_2") (pintype "passive"))
      (node (ref "R40") (pin "1") (pinfunction "1_1") (pintype "passive"))
      (node (ref "R41") (pin "2") (pinfunction "2_2") (pintype "passive"))
      (node (ref "R42") (pin "2") (pinfunction "2_2") (pintype "passive"))
      (node (ref "R43") (pin "2") (pinfunction "2_2") (pintype "passive"))
      (node (ref "R5") (pin "2") (pinfunction "2_2") (pintype "passive"))
      (node (ref "R6") (pin "2") (pinfunction "2_2") (pintype "passive"))
      (node (ref "R7") (pin "2") (pinfunction "2_2") (pintype "passive"))
      (node (ref "R8") (pin "2") (pinfunction "2_2") (pintype "passive"))
      (node (ref "R9") (pin "2") (pinfunction "2_2") (pintype "passive"))
      (node (ref "U1") (pin "48") (pinfunction "VDD_48") (pintype "power_in"))
    )
    (net (code "66") (name "GND") (class "Default")
      (node (ref "C1") (pin "1") (pinfunction "1_1") (pintype "passive"))
      (node (ref "C10") (pin "1") (pinfunction "1_1") (pintype "passive"))
      (node (ref "C11") (pin "1") (pinfunction "1_1") (pintype "passive"))
      (node (ref "C12") (pin "1") (pinfunction "1_1") (pintype "passive"))
      (node (ref "C13") (pin "1") (pinfunction "1_1") (pintype "passive"))
      (node (ref "C14") (pin "1") (pinfunction "1_1") (pintype "passive"))
      (node (ref "C15") (pin "1") (pinfunction "1_1") (pintype "passive"))
      (node (ref "C16") (pin "1") (pinfunction "1_1") (pintype "passive"))
      (node (ref "C17") (pin "1") (pinfunction "1_1") (pintype "passive"))
      (node (ref "C18") (pin "1") (pinfunction "1_1") (pintype "passive"))
      (node (ref "C19") (pin "2") (pinfunction "2_2") (pintype "passive"))
      (node (ref "C2") (pin "1") (pinfunction "1_1") (pintype "passive"))
      (node (ref "C20") (pin "1") (pinfunction "1_1") (pintype "passive"))
      (node (ref "C21") (pin "2") (pinfunction "2_2") (pintype "passive"))
      (node (ref "C3") (pin "1") (pinfunction "1_1") (pintype "passive"))
      (node (ref "C4") (pin "1") (pinfunction "1_1") (pintype "passive"))
      (node (ref "C5") (pin "1") (pinfunction "1_1") (pintype "passive"))
      (node (ref "C6") (pin "1") (pinfunction "1_1") (pintype "passive"))
      (node (ref "C7") (pin "1") (pinfunction "1_1") (pintype "passive"))
      (node (ref "C8") (pin "1") (pinfunction "1_1") (pintype "passive"))
      (node (ref "C9") (pin "1") (pinfunction "1_1") (pintype "passive"))
      (node (ref "COM1") (pin "5") (pinfunction "5_5") (pintype "passive"))
      (node (ref "COM2") (pin "5") (pinfunction "5_5") (pintype "passive"))
      (node (ref "D1") (pin "2") (pinfunction "K_2") (pintype "passive"))
      (node (ref "J1") (pin "3") (pintype "passive"))
      (node (ref "J2") (pin "3") (pintype "passive"))
      (node (ref "J3") (pin "3") (pintype "passive"))
      (node (ref "J4") (pin "3") (pintype "passive"))
      (node (ref "J5") (pin "3") (pintype "passive"))
      (node (ref "J6") (pin "3") (pintype "passive"))
      (node (ref "P1") (pin "5") (pinfunction "5_5") (pintype "passive"))
      (node (ref "P2") (pin "5") (pinfunction "5_5") (pintype "passive"))
      (node (ref "P3") (pin "1") (pinfunction "1_1") (pintype "passive"))
      (node (ref "S1") (pin "5") (pinfunction "B4_5") (pintype "passive"))
      (node (ref "S1") (pin "6") (pinfunction "B3_6") (pintype "passive"))
      (node (ref "S1") (pin "7") (pinfunction "B2_7") (pintype "passive"))
      (node (ref "S1") (pin "8") (pinfunction "B1_8") (pintype "passive"))
      (node (ref "U1") (pin "13") (pinfunction "VSS_13") (pintype "power_in"))
      (node (ref "U1") (pin "24") (pinfunction "VSS_24") (pintype "power_in"))
    )
    (net (code "67") (name "Net-(D1-A)") (class "Default")
      (node (ref "D1") (pin "1") (pinfunction "A_1") (pintype "passive"))
      (node (ref "R41") (pin "1") (pinfunction "1_1") (pintype "passive"))
    )
    (net (code "68") (name "unconnected-(COM1-MH1-Pad10)") (class "Default")
      (node (ref "COM1") (pin "10") (pinfunction "MH1_10") (pintype "passive"))
    )
    (net (code "69") (name "unconnected-(COM1-MH2-Pad11)") (class "Default")
      (node (ref "COM1") (pin "11") (pinfunction "MH2_11") (pintype "passive"))
    )
    (net (code "70") (name "unconnected-(COM1-Pad4)") (class "Default")
      (node (ref "COM1") (pin "4") (pinfunction "4_4") (pintype "passive"))
    )
    (net (code "71") (name "unconnected-(COM1-Pad6)") (class "Default")
      (node (ref "COM1") (pin "6") (pinfunction "6_6") (pintype "passive"))
    )
    (net (code "72") (name "unconnected-(COM1-Pad9)") (class "Default")
      (node (ref "COM1") (pin "9") (pinfunction "9_9") (pintype "passive"))
    )
    (net (code "73") (name "unconnected-(COM2-MH1-Pad10)") (class "Default")
      (node (ref "COM2") (pin "10") (pinfunction "MH1_10") (pintype "passive"))
    )
    (net (code "74") (name "unconnected-(COM2-MH2-Pad11)") (class "Default")
      (node (ref "COM2") (pin "11") (pinfunction "MH2_11") (pintype "passive"))
    )
    (net (code "75") (name "unconnected-(COM2-Pad4)") (class "Default")
      (node (ref "COM2") (pin "4") (pinfunction "4_4") (pintype "passive"))
    )
    (net (code "76") (name "unconnected-(COM2-Pad6)") (class "Default")
      (node (ref "COM2") (pin "6") (pinfunction "6_6") (pintype "passive"))
    )
    (net (code "77") (name "unconnected-(COM2-Pad9)") (class "Default")
      (node (ref "COM2") (pin "9") (pinfunction "9_9") (pintype "passive"))
    )
    (net (code "78") (name "unconnected-(P1-Pad4)") (class "Default")
      (node (ref "P1") (pin "4") (pinfunction "4_4") (pintype "passive"))
    )
    (net (code "79") (name "unconnected-(P1-Pad6)") (class "Default")
      (node (ref "P1") (pin "6") (pinfunction "6_6") (pintype "passive"))
    )
    (net (code "80") (name "unconnected-(P2-Pad4)") (class "Default")
      (node (ref "P2") (pin "4") (pinfunction "4_4") (pintype "passive"))
    )
    (net (code "81") (name "unconnected-(P2-Pad6)") (class "Default")
      (node (ref "P2") (pin "6") (pinfunction "6_6") (pintype "passive"))
    )
    (net (code "82") (name "unconnected-(U1-GPort2_Bit2_PWM0{slash}WD-Pad25)") (class "Default")
      (node (ref "U1") (pin "25") (pinfunction "GPort2_Bit2_PWM0/WD_25") (pintype "passive"))
    )
  )
)
